# mpc57_can.net
KiCad netlist of a schematic drawn in Altium Designer
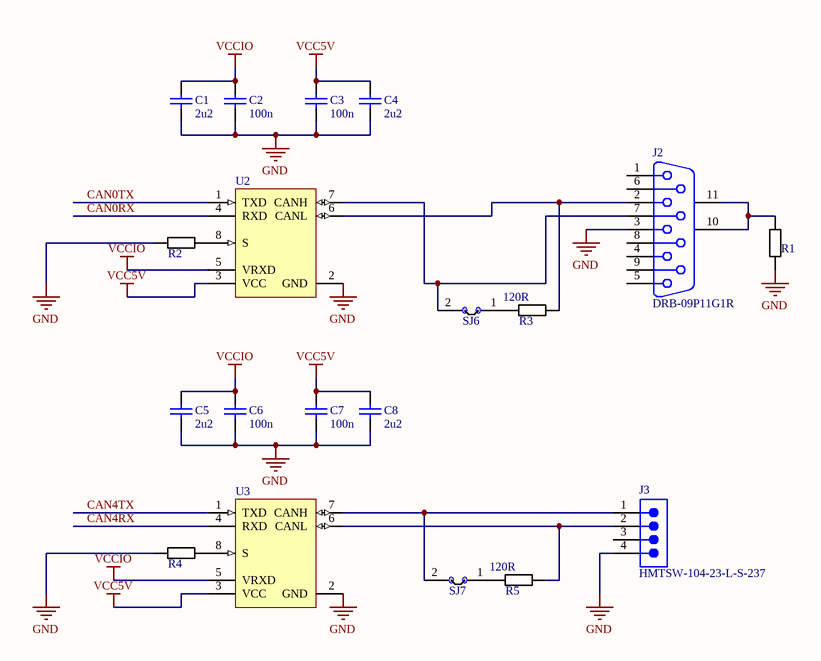
[diagram p0: mpc57_can.SchDoc]

(export (version "E")
  (design (tool "Eeschema 10.0.6"))
  (components
    (comp (ref "C1")
      (value "2u2")
      (footprint "CAPC0603_M")
      (description "2u2, 0603")
      (fields (field (name "PART NUMBER") "CCHIP-2u2-0603"))
      (libsource (lib "NewAE_AltiumLib") (part "CAP"))
    )
    (comp (ref "C2")
      (value "100n")
      (footprint "CAPC0402_M")
      (description "100n, 0402")
      (fields (field (name "PART NUMBER") "CCHIP-100n-0402"))
      (libsource (lib "NewAE_AltiumLib") (part "CAP"))
    )
    (comp (ref "C3")
      (value "100n")
      (footprint "CAPC0402_M")
      (description "100n, 0402")
      (fields (field (name "PART NUMBER") "CCHIP-100n-0402"))
      (libsource (lib "NewAE_AltiumLib") (part "CAP"))
    )
    (comp (ref "C4")
      (value "2u2")
      (footprint "CAPC0603_M")
      (description "2u2, 0603")
      (fields (field (name "PART NUMBER") "CCHIP-2u2-0603"))
      (libsource (lib "NewAE_AltiumLib") (part "CAP"))
    )
    (comp (ref "C5")
      (value "2u2")
      (footprint "CAPC0603_M")
      (description "2u2, 0603")
      (fields (field (name "PART NUMBER") "CCHIP-2u2-0603"))
      (libsource (lib "NewAE_AltiumLib") (part "CAP"))
    )
    (comp (ref "C6")
      (value "100n")
      (footprint "CAPC0402_M")
      (description "100n, 0402")
      (fields (field (name "PART NUMBER") "CCHIP-100n-0402"))
      (libsource (lib "NewAE_AltiumLib") (part "CAP"))
    )
    (comp (ref "C7")
      (value "100n")
      (footprint "CAPC0402_M")
      (description "100n, 0402")
      (fields (field (name "PART NUMBER") "CCHIP-100n-0402"))
      (libsource (lib "NewAE_AltiumLib") (part "CAP"))
    )
    (comp (ref "C8")
      (value "2u2")
      (footprint "CAPC0603_M")
      (description "2u2, 0603")
      (fields (field (name "PART NUMBER") "CCHIP-2u2-0603"))
      (libsource (lib "NewAE_AltiumLib") (part "CAP"))
    )
    (comp (ref "J2")
      (value "DRB-09P11G1R")
      (footprint "TAIT-DRB-09P11G1R_V")
      (description "DB9 R/A Connector, Through-hole, Male")
      (libsource (lib "Altium Content Vault") (part "TAIT-DRB-09P11G1R-9"))
    )
    (comp (ref "J3")
      (value "HMTSW-104-23-L-S-237")
      (footprint "SMTC-HMTSW-104-23-X-S-237")
      (fields (field (name "MANUFACTURER") "Samtec"))
      (libsource (lib "Altium Content Vault") (part "CMP-1024-00020-1"))
    )
    (comp (ref "R1")
      (value "10R")
      (footprint "RESC1608X55N")
      (description "10R res, 0603, 1%, 1/10W")
      (fields (field (name "PART NUMBER") "RCHIP-10R-0603") (field (name "TOLERANCE") "1%"))
      (libsource (lib "") (part "RES-EU_1"))
    )
    (comp (ref "R2")
      (value "4k7")
      (footprint "RESC1608X55N")
      (description "4k7 res, 0603, 1%, 1/10W")
      (fields (field (name "PART NUMBER") "RCHIP-4K7-0603") (field (name "TOLERANCE") "1%"))
      (libsource (lib "NewAE_AltiumLib") (part "RES-EU"))
    )
    (comp (ref "R3")
      (value "120R")
      (footprint "RESC1608X55N")
      (description "120R res, 0603, 1%, 1/10W")
      (fields (field (name "PART NUMBER") "RCHIP-120R-0603") (field (name "TOLERANCE") "1%"))
      (libsource (lib "NewAE_AltiumLib") (part "RES-EU"))
    )
    (comp (ref "R4")
      (value "4k7")
      (footprint "RESC1608X55N")
      (description "4k7 res, 0603, 1%, 1/10W")
      (fields (field (name "PART NUMBER") "RCHIP-4K7-0603") (field (name "TOLERANCE") "1%"))
      (libsource (lib "NewAE_AltiumLib") (part "RES-EU"))
    )
    (comp (ref "R5")
      (value "120R")
      (footprint "RESC1608X55N")
      (description "120R res, 0603, 1%, 1/10W")
      (fields (field (name "PART NUMBER") "RCHIP-120R-0603") (field (name "TOLERANCE") "1%"))
      (libsource (lib "NewAE_AltiumLib") (part "RES-EU"))
    )
    (comp (ref "SJ6")
      (value "NC")
      (footprint "SJ_2S_NC")
      (description "Solder Jumper, NC")
      (fields (field (name "PART NUMBER") "SJ_2S"))
      (libsource (lib "NewAE_AltiumLib") (part "SJ_2S"))
    )
    (comp (ref "SJ7")
      (value "NC")
      (footprint "SJ_2S_NC")
      (description "Solder Jumper, NC")
      (fields (field (name "PART NUMBER") "SJ_2S"))
      (libsource (lib "NewAE_AltiumLib") (part "SJ_2S"))
    )
    (comp (ref "U2")
      (value "TJA1051T/3")
      (footprint "SOIC8_NARROW")
      (description "CAN-FD Transceiver, 3.3V")
      (fields (field (name "PART NUMBER") "TJA1051T_3"))
      (libsource (lib "NewAE_AltiumLib") (part "CAN8SOIC_VCCIOPIN5"))
    )
    (comp (ref "U3")
      (value "TJA1051T/3")
      (footprint "SOIC8_NARROW")
      (description "CAN-FD Transceiver, 3.3V")
      (fields (field (name "PART NUMBER") "TJA1051T_3"))
      (libsource (lib "NewAE_AltiumLib") (part "CAN8SOIC_VCCIOPIN5"))
    )
  )
  (nets
    (net (code "1") (name "/CAN0RX") (class "Default")
      (node (ref "U2") (pin "4") (pinfunction "RXD_4") (pintype "tri_state"))
    )
    (net (code "2") (name "/CAN0TX") (class "Default")
      (node (ref "U2") (pin "1") (pinfunction "TXD_1") (pintype "input"))
    )
    (net (code "3") (name "/CAN4RX") (class "Default")
      (node (ref "U3") (pin "4") (pinfunction "RXD_4") (pintype "tri_state"))
    )
    (net (code "4") (name "/CAN4TX") (class "Default")
      (node (ref "U3") (pin "1") (pinfunction "TXD_1") (pintype "input"))
    )
    (net (code "5") (name "GND") (class "Default")
      (node (ref "C1") (pin "2") (pinfunction "2_2") (pintype "passive"))
      (node (ref "C2") (pin "2") (pinfunction "2_2") (pintype "passive"))
      (node (ref "C3") (pin "2") (pinfunction "2_2") (pintype "passive"))
      (node (ref "C4") (pin "2") (pinfunction "2_2") (pintype "passive"))
      (node (ref "C5") (pin "2") (pinfunction "2_2") (pintype "passive"))
      (node (ref "C6") (pin "2") (pinfunction "2_2") (pintype "passive"))
      (node (ref "C7") (pin "2") (pinfunction "2_2") (pintype "passive"))
      (node (ref "C8") (pin "2") (pinfunction "2_2") (pintype "passive"))
      (node (ref "J2") (pin "3") (pinfunction "3_3") (pintype "passive"))
      (node (ref "J3") (pin "4") (pinfunction "4_4") (pintype "passive"))
      (node (ref "R1") (pin "1") (pinfunction "1_1") (pintype "passive"))
      (node (ref "R2") (pin "1") (pinfunction "1_1") (pintype "passive"))
      (node (ref "R4") (pin "1") (pinfunction "1_1") (pintype "passive"))
      (node (ref "U2") (pin "2") (pinfunction "GND_2") (pintype "power_in"))
      (node (ref "U3") (pin "2") (pinfunction "GND_2") (pintype "power_in"))
    )
    (net (code "6") (name "Net-(J2-MH1)") (class "Default")
      (node (ref "J2") (pin "10") (pinfunction "MH1_10") (pintype "passive"))
      (node (ref "J2") (pin "11") (pinfunction "MH2_11") (pintype "passive"))
      (node (ref "R1") (pin "2") (pinfunction "2_2") (pintype "passive"))
    )
    (net (code "7") (name "Net-(R3-Pad1)") (class "Default")
      (node (ref "R3") (pin "1") (pinfunction "1_1") (pintype "passive"))
      (node (ref "SJ6") (pin "1") (pinfunction "1_1") (pintype "passive"))
    )
    (net (code "8") (name "Net-(R5-Pad1)") (class "Default")
      (node (ref "R5") (pin "1") (pinfunction "1_1") (pintype "passive"))
      (node (ref "SJ7") (pin "1") (pinfunction "1_1") (pintype "passive"))
    )
    (net (code "9") (name "Net-(U2-CANH)") (class "Default")
      (node (ref "J2") (pin "7") (pinfunction "7_7") (pintype "passive"))
      (node (ref "SJ6") (pin "2") (pinfunction "2_2") (pintype "passive"))
      (node (ref "U2") (pin "7") (pinfunction "CANH_7") (pintype "bidirectional"))
    )
    (net (code "10") (name "Net-(U2-CANL)") (class "Default")
      (node (ref "J2") (pin "2") (pinfunction "2_2") (pintype "passive"))
      (node (ref "R3") (pin "2") (pinfunction "2_2") (pintype "passive"))
      (node (ref "U2") (pin "6") (pinfunction "CANL_6") (pintype "bidirectional"))
    )
    (net (code "11") (name "Net-(U2-S)") (class "Default")
      (node (ref "R2") (pin "2") (pinfunction "2_2") (pintype "passive"))
      (node (ref "U2") (pin "8") (pinfunction "S_8") (pintype "input"))
    )
    (net (code "12") (name "Net-(U3-CANH)") (class "Default")
      (node (ref "J3") (pin "1") (pinfunction "1_1") (pintype "passive"))
      (node (ref "SJ7") (pin "2") (pinfunction "2_2") (pintype "passive"))
      (node (ref "U3") (pin "7") (pinfunction "CANH_7") (pintype "bidirectional"))
    )
    (net (code "13") (name "Net-(U3-CANL)") (class "Default")
      (node (ref "J3") (pin "2") (pinfunction "2_2") (pintype "passive"))
      (node (ref "R5") (pin "2") (pinfunction "2_2") (pintype "passive"))
      (node (ref "U3") (pin "6") (pinfunction "CANL_6") (pintype "bidirectional"))
    )
    (net (code "14") (name "Net-(U3-S)") (class "Default")
      (node (ref "R4") (pin "2") (pinfunction "2_2") (pintype "passive"))
      (node (ref "U3") (pin "8") (pinfunction "S_8") (pintype "input"))
    )
    (net (code "15") (name "VCC5V") (class "Default")
      (node (ref "C3") (pin "1") (pinfunction "1_1") (pintype "passive"))
      (node (ref "C4") (pin "1") (pinfunction "1_1") (pintype "passive"))
      (node (ref "C7") (pin "1") (pinfunction "1_1") (pintype "passive"))
      (node (ref "C8") (pin "1") (pinfunction "1_1") (pintype "passive"))
      (node (ref "U2") (pin "3") (pinfunction "VCC_3") (pintype "power_in"))
      (node (ref "U3") (pin "3") (pinfunction "VCC_3") (pintype "power_in"))
    )
    (net (code "16") (name "VCCIO") (class "Default")
      (node (ref "C1") (pin "1") (pinfunction "1_1") (pintype "passive"))
      (node (ref "C2") (pin "1") (pinfunction "1_1") (pintype "passive"))
      (node (ref "C5") (pin "1") (pinfunction "1_1") (pintype "passive"))
      (node (ref "C6") (pin "1") (pinfunction "1_1") (pintype "passive"))
      (node (ref "U2") (pin "5") (pinfunction "VRXD_5") (pintype "power_in"))
      (node (ref "U3") (pin "5") (pinfunction "VRXD_5") (pintype "power_in"))
    )
    (net (code "17") (name "unconnected-(J2-Pad1)") (class "Default")
      (node (ref "J2") (pin "1") (pinfunction "1_1") (pintype "passive"))
    )
    (net (code "18") (name "unconnected-(J2-Pad4)") (class "Default")
      (node (ref "J2") (pin "4") (pinfunction "4_4") (pintype "passive"))
    )
    (net (code "19") (name "unconnected-(J2-Pad5)") (class "Default")
      (node (ref "J2") (pin "5") (pinfunction "5_5") (pintype "passive"))
    )
    (net (code "20") (name "unconnected-(J2-Pad6)") (class "Default")
      (node (ref "J2") (pin "6") (pinfunction "6_6") (pintype "passive"))
    )
    (net (code "21") (name "unconnected-(J2-Pad8)") (class "Default")
      (node (ref "J2") (pin "8") (pinfunction "8_8") (pintype "passive"))
    )
    (net (code "22") (name "unconnected-(J2-Pad9)") (class "Default")
      (node (ref "J2") (pin "9") (pinfunction "9_9") (pintype "passive"))
    )
    (net (code "23") (name "unconnected-(J3-Pad3)") (class "Default")
      (node (ref "J3") (pin "3") (pinfunction "3_3") (pintype "passive"))
    )
  )
)
